# Transistor_controlled_bell_switch_with_c.net
KiCad netlist of a schematic drawn in EAGLE
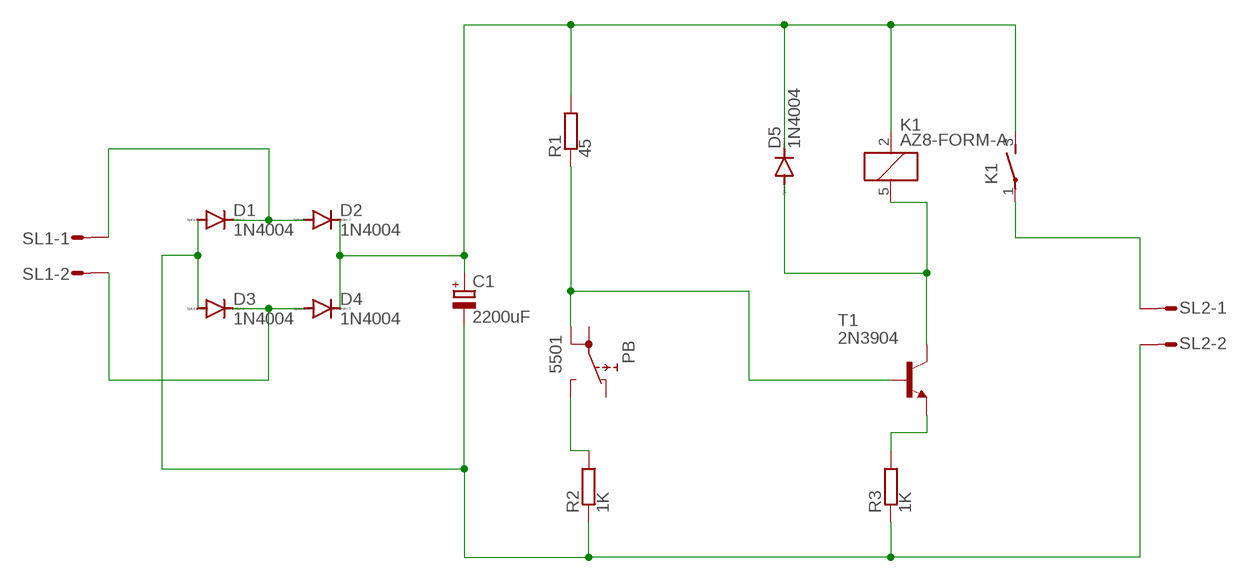
[diagram p0: schematic, sheet 1]

(export (version "E")
  (design (tool "Eeschema 10.0.6"))
  (components
    (comp (ref "C1")
      (value "2200uF")
      (footprint "eagle-import:085CS_1AR")
      (libsource (lib "eagle-import") (part "CPOL-EU085CS-1AR"))
    )
    (comp (ref "D1")
      (value "1N4004")
      (footprint "eagle-import:DO41-10")
      (libsource (lib "eagle-import") (part "1N4004"))
    )
    (comp (ref "D2")
      (value "1N4004")
      (footprint "eagle-import:DO41-10")
      (libsource (lib "eagle-import") (part "1N4004"))
    )
    (comp (ref "D3")
      (value "1N4004")
      (footprint "eagle-import:DO41-10")
      (libsource (lib "eagle-import") (part "1N4004"))
    )
    (comp (ref "D4")
      (value "1N4004")
      (footprint "eagle-import:DO41-10")
      (libsource (lib "eagle-import") (part "1N4004"))
    )
    (comp (ref "D5")
      (value "1N4004")
      (footprint "eagle-import:DO41-10")
      (libsource (lib "eagle-import") (part "1N4004"))
    )
    (comp (ref "K1")
      (value "AZ8-FORM-A")
      (footprint "eagle-import:AZ8")
      (libsource (lib "eagle-import") (part "AZ8-FORM-A"))
    )
    (comp (ref "PB")
      (value "5501")
      (footprint "eagle-import:5501")
      (libsource (lib "eagle-import") (part "55?01"))
    )
    (comp (ref "R1")
      (value "45")
      (footprint "eagle-import:PMD")
      (libsource (lib "eagle-import") (part "PMD"))
    )
    (comp (ref "R2")
      (value "1K")
      (footprint "eagle-import:PMD")
      (libsource (lib "eagle-import") (part "PMD"))
    )
    (comp (ref "R3")
      (value "1K")
      (footprint "eagle-import:PMD")
      (libsource (lib "eagle-import") (part "PMD"))
    )
    (comp (ref "SL1")
      (value "M02S")
      (footprint "eagle-import:02P")
      (libsource (lib "eagle-import") (part "M02S"))
    )
    (comp (ref "SL2")
      (value "M02S")
      (footprint "eagle-import:02P")
      (libsource (lib "eagle-import") (part "M02S"))
    )
    (comp (ref "T1")
      (value "2N3904")
      (footprint "eagle-import:TO92")
      (libsource (lib "eagle-import") (part "2N3904"))
    )
  )
  (nets
    (net (code "1") (name "Net-(K1A-P)") (class "Default")
      (node (ref "K1") (pin "1") (pinfunction "P_1") (pintype "passive"))
      (node (ref "SL2") (pin "1") (pinfunction "S_1") (pintype "passive"))
    )
    (net (code "2") (name "Net-(K1A-S)") (class "Default")
      (node (ref "C1") (pin "+") (pinfunction "+_+") (pintype "passive"))
      (node (ref "D2") (pin "C") (pinfunction "C_C") (pintype "passive"))
      (node (ref "D4") (pin "C") (pinfunction "C_C") (pintype "passive"))
      (node (ref "D5") (pin "C") (pinfunction "C_C") (pintype "passive"))
      (node (ref "K1") (pin "2") (pinfunction "1_2") (pintype "passive"))
      (node (ref "K1") (pin "3") (pinfunction "S_3") (pintype "passive"))
      (node (ref "R1") (pin "1") (pinfunction "1_1") (pintype "passive"))
    )
    (net (code "3") (name "Net-(K1B-2)") (class "Default")
      (node (ref "D5") (pin "A") (pinfunction "A_A") (pintype "passive"))
      (node (ref "K1") (pin "5") (pinfunction "2_5") (pintype "passive"))
      (node (ref "T1") (pin "1") (pinfunction "C_1") (pintype "passive"))
    )
    (net (code "4") (name "Net-(PB-PadNO)") (class "Default")
      (node (ref "PB") (pin "NO") (pinfunction "NO_NO") (pintype "passive"))
      (node (ref "R2") (pin "1") (pinfunction "1_1") (pintype "passive"))
    )
    (net (code "5") (name "Net-(SL1A-S)") (class "Default")
      (node (ref "D1") (pin "C") (pinfunction "C_C") (pintype "passive"))
      (node (ref "D2") (pin "A") (pinfunction "A_A") (pintype "passive"))
      (node (ref "SL1") (pin "1") (pinfunction "S_1") (pintype "passive"))
    )
    (net (code "6") (name "Net-(SL1B-S)") (class "Default")
      (node (ref "D3") (pin "C") (pinfunction "C_C") (pintype "passive"))
      (node (ref "D4") (pin "A") (pinfunction "A_A") (pintype "passive"))
      (node (ref "SL1") (pin "2") (pinfunction "S_2") (pintype "passive"))
    )
    (net (code "7") (name "Net-(SL2B-S)") (class "Default")
      (node (ref "C1") (pin "-") (pinfunction "-_-") (pintype "passive"))
      (node (ref "D1") (pin "A") (pinfunction "A_A") (pintype "passive"))
      (node (ref "D3") (pin "A") (pinfunction "A_A") (pintype "passive"))
      (node (ref "R2") (pin "2") (pinfunction "2_2") (pintype "passive"))
      (node (ref "R3") (pin "2") (pinfunction "2_2") (pintype "passive"))
      (node (ref "SL2") (pin "2") (pinfunction "S_2") (pintype "passive"))
    )
    (net (code "8") (name "Net-(T1-B)") (class "Default")
      (node (ref "PB") (pin "1B") (pinfunction "1B_1B") (pintype "passive"))
      (node (ref "R1") (pin "2") (pinfunction "2_2") (pintype "passive"))
      (node (ref "T1") (pin "2") (pinfunction "B_2") (pintype "passive"))
    )
    (net (code "9") (name "Net-(T1-E)") (class "Default")
      (node (ref "R3") (pin "1") (pinfunction "1_1") (pintype "passive"))
      (node (ref "T1") (pin "3") (pinfunction "E_3") (pintype "passive"))
    )
    (net (code "10") (name "unconnected-(PB-Pad1A)") (class "Default")
      (node (ref "PB") (pin "1A") (pinfunction "1A_1A") (pintype "passive"))
    )
    (net (code "11") (name "unconnected-(PB-PadNC)") (class "Default")
      (node (ref "PB") (pin "NC") (pinfunction "NC_NC") (pintype "passive"))
    )
  )
)
